# dimmerPower5.net
KiCad netlist of a schematic drawn in EAGLE
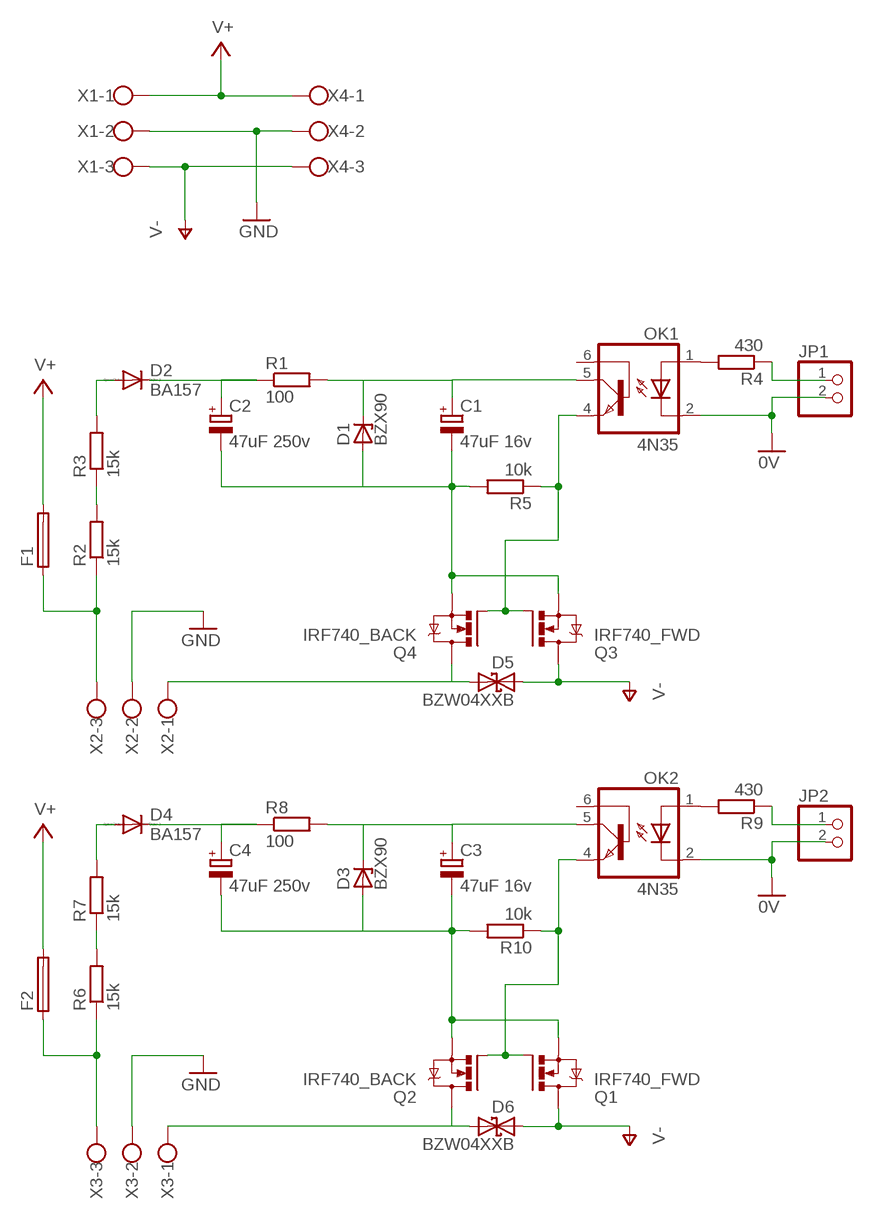
[diagram p0: schematic, sheet 1]

(export (version "E")
  (design (tool "Eeschema 10.0.6"))
  (components
    (comp (ref "C1")
      (value "47uF 16v")
      (footprint "eagle-import:E2,5-6")
      (libsource (lib "eagle-import") (part "CPOL-EUE2.5-6"))
    )
    (comp (ref "C2")
      (value "47uF 250v")
      (footprint "eagle-import:E5-13")
      (libsource (lib "eagle-import") (part "CPOL-EUE5-13"))
    )
    (comp (ref "C3")
      (value "47uF 16v")
      (footprint "eagle-import:E2,5-6")
      (libsource (lib "eagle-import") (part "CPOL-EUE2.5-6"))
    )
    (comp (ref "C4")
      (value "47uF 250v")
      (footprint "eagle-import:E5-13")
      (libsource (lib "eagle-import") (part "CPOL-EUE5-13"))
    )
    (comp (ref "D1")
      (value "BZX90")
      (footprint "eagle-import:DO34Z7")
      (libsource (lib "eagle-import") (part "BZX90"))
    )
    (comp (ref "D2")
      (value "BA157")
      (footprint "eagle-import:P1-10")
      (libsource (lib "eagle-import") (part "BA157"))
    )
    (comp (ref "D3")
      (value "BZX90")
      (footprint "eagle-import:DO34Z7")
      (libsource (lib "eagle-import") (part "BZX90"))
    )
    (comp (ref "D4")
      (value "BA157")
      (footprint "eagle-import:P1-10")
      (libsource (lib "eagle-import") (part "BA157"))
    )
    (comp (ref "D5")
      (value "BZW04XXB")
      (footprint "eagle-import:F126Z12")
      (libsource (lib "eagle-import") (part "BZW04XXB"))
    )
    (comp (ref "D6")
      (value "BZW04XXB")
      (footprint "eagle-import:F126Z12")
      (libsource (lib "eagle-import") (part "BZW04XXB"))
    )
    (comp (ref "F1")
      (value "SH22,5")
      (footprint "eagle-import:SH22,5")
      (fields (field (name "MF") "SCHURTER") (field (name "MPN") "0031.8201"))
      (libsource (lib "eagle-import") (part "SH22,5"))
    )
    (comp (ref "F2")
      (value "SH22,5")
      (footprint "eagle-import:SH22,5")
      (fields (field (name "MF") "SCHURTER") (field (name "MPN") "0031.8201"))
      (libsource (lib "eagle-import") (part "SH22,5"))
    )
    (comp (ref "JP1")
      (value "PINHD-1X2")
      (footprint "eagle-import:1X02")
      (libsource (lib "eagle-import") (part "PINHD-1X2"))
    )
    (comp (ref "JP2")
      (value "PINHD-1X2")
      (footprint "eagle-import:1X02")
      (libsource (lib "eagle-import") (part "PINHD-1X2"))
    )
    (comp (ref "OK1")
      (value "4N35")
      (footprint "eagle-import:DIL06")
      (fields (field (name "MF") "FAIRCHILD SEMICONDUCTOR"))
      (libsource (lib "eagle-import") (part "4N35"))
    )
    (comp (ref "OK2")
      (value "4N35")
      (footprint "eagle-import:DIL06")
      (fields (field (name "MF") "FAIRCHILD SEMICONDUCTOR"))
      (libsource (lib "eagle-import") (part "4N35"))
    )
    (comp (ref "Q1")
      (value "IRF740_FWD")
      (footprint "eagle-import:TO220BV_FWD")
      (libsource (lib "eagle-import") (part "IRF740_FWD"))
    )
    (comp (ref "Q2")
      (value "IRF740_BACK")
      (footprint "eagle-import:TO220BV_BACK")
      (libsource (lib "eagle-import") (part "IRF740_BACK"))
    )
    (comp (ref "Q3")
      (value "IRF740_FWD")
      (footprint "eagle-import:TO220BV_FWD")
      (libsource (lib "eagle-import") (part "IRF740_FWD"))
    )
    (comp (ref "Q4")
      (value "IRF740_BACK")
      (footprint "eagle-import:TO220BV_BACK")
      (libsource (lib "eagle-import") (part "IRF740_BACK"))
    )
    (comp (ref "R1")
      (value "100")
      (footprint "eagle-import:0204_7")
      (libsource (lib "eagle-import") (part "R-EU_0204/7"))
    )
    (comp (ref "R2")
      (value "15k")
      (footprint "eagle-import:P0613_15")
      (libsource (lib "eagle-import") (part "R-EU_0613/15"))
    )
    (comp (ref "R3")
      (value "15k")
      (footprint "eagle-import:P0613_15")
      (libsource (lib "eagle-import") (part "R-EU_0613/15"))
    )
    (comp (ref "R4")
      (value "430")
      (footprint "eagle-import:0204_7")
      (libsource (lib "eagle-import") (part "R-EU_0204/7"))
    )
    (comp (ref "R5")
      (value "10k")
      (footprint "eagle-import:0204_7")
      (libsource (lib "eagle-import") (part "R-EU_0204/7"))
    )
    (comp (ref "R6")
      (value "15k")
      (footprint "eagle-import:P0613_15")
      (libsource (lib "eagle-import") (part "R-EU_0613/15"))
    )
    (comp (ref "R7")
      (value "15k")
      (footprint "eagle-import:P0613_15")
      (libsource (lib "eagle-import") (part "R-EU_0613/15"))
    )
    (comp (ref "R8")
      (value "100")
      (footprint "eagle-import:0204_7")
      (libsource (lib "eagle-import") (part "R-EU_0204/7"))
    )
    (comp (ref "R9")
      (value "430")
      (footprint "eagle-import:0204_7")
      (libsource (lib "eagle-import") (part "R-EU_0204/7"))
    )
    (comp (ref "R10")
      (value "10k")
      (footprint "eagle-import:0204_7")
      (libsource (lib "eagle-import") (part "R-EU_0204/7"))
    )
    (comp (ref "X1")
      (value "W237-103")
      (footprint "eagle-import:W237-103")
      (fields (field (name "MPN") "237-103"))
      (libsource (lib "eagle-import") (part "W237-103"))
    )
    (comp (ref "X2")
      (value "W237-103")
      (footprint "eagle-import:W237-103")
      (fields (field (name "MPN") "237-103"))
      (libsource (lib "eagle-import") (part "W237-103"))
    )
    (comp (ref "X3")
      (value "W237-103")
      (footprint "eagle-import:W237-103")
      (fields (field (name "MPN") "237-103"))
      (libsource (lib "eagle-import") (part "W237-103"))
    )
    (comp (ref "X4")
      (value "W237-103")
      (footprint "eagle-import:W237-103")
      (fields (field (name "MPN") "237-103"))
      (libsource (lib "eagle-import") (part "W237-103"))
    )
  )
  (nets
    (net (code "1") (name "0V") (class "Default")
      (node (ref "JP1") (pin "2") (pinfunction "2_2") (pintype "passive"))
      (node (ref "JP2") (pin "2") (pinfunction "2_2") (pintype "passive"))
      (node (ref "OK1") (pin "2") (pinfunction "C_2") (pintype "passive"))
      (node (ref "OK2") (pin "2") (pinfunction "C_2") (pintype "passive"))
    )
    (net (code "2") (name "GND") (class "Default")
      (node (ref "X1") (pin "2") (pinfunction "KL_2") (pintype "passive"))
      (node (ref "X2") (pin "2") (pinfunction "KL_2") (pintype "passive"))
      (node (ref "X3") (pin "2") (pinfunction "KL_2") (pintype "passive"))
      (node (ref "X4") (pin "2") (pinfunction "KL_2") (pintype "passive"))
    )
    (net (code "3") (name "Net-(C1-Pad-)") (class "Default")
      (node (ref "C1") (pin "-") (pinfunction "-_-") (pintype "passive"))
      (node (ref "C2") (pin "-") (pinfunction "-_-") (pintype "passive"))
      (node (ref "D1") (pin "A") (pinfunction "A_A") (pintype "passive"))
      (node (ref "Q3") (pin "S") (pinfunction "S_S") (pintype "passive"))
      (node (ref "Q4") (pin "S") (pinfunction "S_S") (pintype "passive"))
      (node (ref "R5") (pin "2") (pinfunction "2_2") (pintype "passive"))
    )
    (net (code "4") (name "Net-(C2-Pad+)") (class "Default")
      (node (ref "C2") (pin "+") (pinfunction "+_+") (pintype "passive"))
      (node (ref "D2") (pin "C") (pinfunction "C_C") (pintype "passive"))
      (node (ref "R1") (pin "1") (pinfunction "1_1") (pintype "passive"))
    )
    (net (code "5") (name "Net-(C3-Pad-)") (class "Default")
      (node (ref "C3") (pin "-") (pinfunction "-_-") (pintype "passive"))
      (node (ref "C4") (pin "-") (pinfunction "-_-") (pintype "passive"))
      (node (ref "D3") (pin "A") (pinfunction "A_A") (pintype "passive"))
      (node (ref "Q1") (pin "S") (pinfunction "S_S") (pintype "passive"))
      (node (ref "Q2") (pin "S") (pinfunction "S_S") (pintype "passive"))
      (node (ref "R10") (pin "2") (pinfunction "2_2") (pintype "passive"))
    )
    (net (code "6") (name "Net-(C4-Pad+)") (class "Default")
      (node (ref "C4") (pin "+") (pinfunction "+_+") (pintype "passive"))
      (node (ref "D4") (pin "C") (pinfunction "C_C") (pintype "passive"))
      (node (ref "R8") (pin "1") (pinfunction "1_1") (pintype "passive"))
    )
    (net (code "7") (name "Net-(D2-PadA)") (class "Default")
      (node (ref "D2") (pin "A") (pinfunction "A_A") (pintype "passive"))
      (node (ref "R3") (pin "2") (pinfunction "2_2") (pintype "passive"))
    )
    (net (code "8") (name "Net-(D4-PadA)") (class "Default")
      (node (ref "D4") (pin "A") (pinfunction "A_A") (pintype "passive"))
      (node (ref "R7") (pin "2") (pinfunction "2_2") (pintype "passive"))
    )
    (net (code "9") (name "Net-(D5-2)") (class "Default")
      (node (ref "D5") (pin "C") (pinfunction "2_C") (pintype "passive"))
      (node (ref "Q4") (pin "D") (pinfunction "D_D") (pintype "passive"))
      (node (ref "X2") (pin "1") (pinfunction "KL_1") (pintype "passive"))
    )
    (net (code "10") (name "Net-(D6-2)") (class "Default")
      (node (ref "D6") (pin "C") (pinfunction "2_C") (pintype "passive"))
      (node (ref "Q2") (pin "D") (pinfunction "D_D") (pintype "passive"))
      (node (ref "X3") (pin "1") (pinfunction "KL_1") (pintype "passive"))
    )
    (net (code "11") (name "Net-(JP1-Pad1)") (class "Default")
      (node (ref "JP1") (pin "1") (pinfunction "1_1") (pintype "passive"))
      (node (ref "R4") (pin "1") (pinfunction "1_1") (pintype "passive"))
    )
    (net (code "12") (name "Net-(JP2-Pad1)") (class "Default")
      (node (ref "JP2") (pin "1") (pinfunction "1_1") (pintype "passive"))
      (node (ref "R9") (pin "1") (pinfunction "1_1") (pintype "passive"))
    )
    (net (code "13") (name "Net-(OK1-A)") (class "Default")
      (node (ref "OK1") (pin "1") (pinfunction "A_1") (pintype "passive"))
      (node (ref "R4") (pin "2") (pinfunction "2_2") (pintype "passive"))
    )
    (net (code "14") (name "Net-(OK1-COL)") (class "Default")
      (node (ref "C1") (pin "+") (pinfunction "+_+") (pintype "passive"))
      (node (ref "D1") (pin "C") (pinfunction "C_C") (pintype "passive"))
      (node (ref "OK1") (pin "5") (pinfunction "COL_5") (pintype "passive"))
      (node (ref "R1") (pin "2") (pinfunction "2_2") (pintype "passive"))
    )
    (net (code "15") (name "Net-(OK1-EMI)") (class "Default")
      (node (ref "OK1") (pin "4") (pinfunction "EMI_4") (pintype "passive"))
      (node (ref "Q3") (pin "G") (pinfunction "G_G") (pintype "passive"))
      (node (ref "Q4") (pin "G") (pinfunction "G_G") (pintype "passive"))
      (node (ref "R5") (pin "1") (pinfunction "1_1") (pintype "passive"))
    )
    (net (code "16") (name "Net-(OK2-A)") (class "Default")
      (node (ref "OK2") (pin "1") (pinfunction "A_1") (pintype "passive"))
      (node (ref "R9") (pin "2") (pinfunction "2_2") (pintype "passive"))
    )
    (net (code "17") (name "Net-(OK2-COL)") (class "Default")
      (node (ref "C3") (pin "+") (pinfunction "+_+") (pintype "passive"))
      (node (ref "D3") (pin "C") (pinfunction "C_C") (pintype "passive"))
      (node (ref "OK2") (pin "5") (pinfunction "COL_5") (pintype "passive"))
      (node (ref "R8") (pin "2") (pinfunction "2_2") (pintype "passive"))
    )
    (net (code "18") (name "Net-(OK2-EMI)") (class "Default")
      (node (ref "OK2") (pin "4") (pinfunction "EMI_4") (pintype "passive"))
      (node (ref "Q1") (pin "G") (pinfunction "G_G") (pintype "passive"))
      (node (ref "Q2") (pin "G") (pinfunction "G_G") (pintype "passive"))
      (node (ref "R10") (pin "1") (pinfunction "1_1") (pintype "passive"))
    )
    (net (code "19") (name "Net-(R2-Pad2)") (class "Default")
      (node (ref "R2") (pin "2") (pinfunction "2_2") (pintype "passive"))
      (node (ref "R3") (pin "1") (pinfunction "1_1") (pintype "passive"))
    )
    (net (code "20") (name "Net-(R6-Pad2)") (class "Default")
      (node (ref "R6") (pin "2") (pinfunction "2_2") (pintype "passive"))
      (node (ref "R7") (pin "1") (pinfunction "1_1") (pintype "passive"))
    )
    (net (code "21") (name "Net-(X2C-KL)") (class "Default")
      (node (ref "F1") (pin "1") (pinfunction "1_1") (pintype "passive"))
      (node (ref "R2") (pin "1") (pinfunction "1_1") (pintype "passive"))
      (node (ref "X2") (pin "3") (pinfunction "KL_3") (pintype "passive"))
    )
    (net (code "22") (name "Net-(X3C-KL)") (class "Default")
      (node (ref "F2") (pin "1") (pinfunction "1_1") (pintype "passive"))
      (node (ref "R6") (pin "1") (pinfunction "1_1") (pintype "passive"))
      (node (ref "X3") (pin "3") (pinfunction "KL_3") (pintype "passive"))
    )
    (net (code "23") (name "V+") (class "Default")
      (node (ref "F1") (pin "2") (pinfunction "2_2") (pintype "passive"))
      (node (ref "F2") (pin "2") (pinfunction "2_2") (pintype "passive"))
      (node (ref "X1") (pin "1") (pinfunction "KL_1") (pintype "passive"))
      (node (ref "X4") (pin "1") (pinfunction "KL_1") (pintype "passive"))
    )
    (net (code "24") (name "V-") (class "Default")
      (node (ref "D5") (pin "A") (pinfunction "1_A") (pintype "passive"))
      (node (ref "D6") (pin "A") (pinfunction "1_A") (pintype "passive"))
      (node (ref "Q1") (pin "D") (pinfunction "D_D") (pintype "passive"))
      (node (ref "Q3") (pin "D") (pinfunction "D_D") (pintype "passive"))
      (node (ref "X1") (pin "3") (pinfunction "KL_3") (pintype "passive"))
      (node (ref "X4") (pin "3") (pinfunction "KL_3") (pintype "passive"))
    )
    (net (code "25") (name "unconnected-(OK1-BAS-Pad6)") (class "Default")
      (node (ref "OK1") (pin "6") (pinfunction "BAS_6") (pintype "passive"))
    )
    (net (code "26") (name "unconnected-(OK2-BAS-Pad6)") (class "Default")
      (node (ref "OK2") (pin "6") (pinfunction "BAS_6") (pintype "passive"))
    )
  )
)
